# Power_5V.net
KiCad netlist of a schematic drawn in Altium Designer
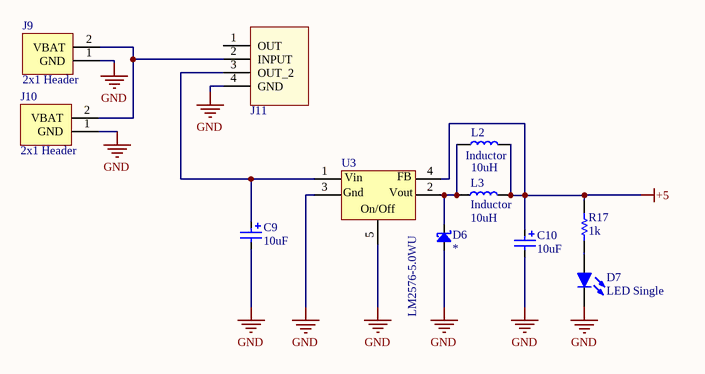
[diagram p0: Power 5V.SchDoc]

(export (version "E")
  (design (tool "Eeschema 10.0.6"))
  (components
    (comp (ref "C9")
      (value "10uF")
      (footprint "Capacitor Through Hole 5x11")
      (description "Capacitor")
      (libsource (lib "RK_Lib") (part "Capacitor Polarized"))
    )
    (comp (ref "C10")
      (value "10uF")
      (footprint "Through hole Capacitor 16V 470uF")
      (description "Capacitor")
      (libsource (lib "RK_Lib") (part "Capacitor Polarized"))
    )
    (comp (ref "D6")
      (value "*")
      (footprint "Schottky Rectifier diode")
      (description "Diode Schottky")
      (libsource (lib "RK_Lib") (part "Diode Schottky"))
    )
    (comp (ref "D7")
      (value "LED Single")
      (footprint "LED 0603")
      (description "LED")
      (libsource (lib "RK_Lib") (part "LED Single"))
    )
    (comp (ref "J9")
      (value "2x1 Header")
      (footprint "Header 1x2 2.54mm")
      (libsource (lib "RK_Lib") (part "2x1 Header (power)"))
    )
    (comp (ref "J10")
      (value "2x1 Header")
      (footprint "Header 1x2 2.54mm")
      (libsource (lib "RK_Lib") (part "2x1 Header (power)"))
    )
    (comp (ref "J11")
      (value "Power Switch")
      (footprint "POWER SWITCH")
      (libsource (lib "RK_Lib") (part "Power Switch"))
    )
    (comp (ref "L2")
      (value "Inductor")
      (footprint "Inductor 12.5x12.5x6mm")
      (fields (field (name "ALTIUM_VALUE") "10uH"))
      (libsource (lib "RK_Lib") (part "Inductor"))
    )
    (comp (ref "L3")
      (value "Inductor")
      (footprint "Inductor 12.5x12.5x6mm")
      (fields (field (name "ALTIUM_VALUE") "10uH"))
      (libsource (lib "RK_Lib") (part "Inductor"))
    )
    (comp (ref "R17")
      (value "1k")
      (footprint "R 0603")
      (description "Resistor")
      (libsource (lib "RK_Lib") (part "Res"))
    )
    (comp (ref "U3")
      (value "LM2576-5.0WU")
      (footprint "5V 3A REG")
      (description "IC REG BUCK 5V 3A TO263-5")
      (fields (field (name "MANUFACTURER") "Microchip Micrel"))
      (libsource (lib "RK_Lib") (part "LM2576-5.0WU"))
    )
  )
  (nets
    (net (code "1") (name "+5") (class "Default")
      (node (ref "C10") (pin "1") (pinfunction "1_1") (pintype "passive"))
      (node (ref "L2") (pin "2") (pinfunction "2_2") (pintype "passive"))
      (node (ref "L3") (pin "2") (pinfunction "2_2") (pintype "passive"))
      (node (ref "R17") (pin "1") (pinfunction "1_1") (pintype "passive"))
      (node (ref "U3") (pin "4") (pinfunction "4_4") (pintype "passive"))
    )
    (net (code "2") (name "GND") (class "Default")
      (node (ref "C10") (pin "2") (pinfunction "2_2") (pintype "passive"))
      (node (ref "C9") (pin "2") (pinfunction "2_2") (pintype "passive"))
      (node (ref "D6") (pin "2") (pinfunction "A_2") (pintype "passive"))
      (node (ref "D7") (pin "2") (pinfunction "K_2") (pintype "passive"))
      (node (ref "J10") (pin "1") (pinfunction "GND_1") (pintype "power_in"))
      (node (ref "J11") (pin "4") (pinfunction "GND_4") (pintype "passive"))
      (node (ref "J9") (pin "1") (pinfunction "GND_1") (pintype "power_in"))
      (node (ref "U3") (pin "3") (pinfunction "3_3") (pintype "passive"))
      (node (ref "U3") (pin "5") (pinfunction "5_5") (pintype "passive"))
    )
    (net (code "3") (name "Net-(D6-K)") (class "Default")
      (node (ref "D6") (pin "1") (pinfunction "K_1") (pintype "passive"))
      (node (ref "L2") (pin "1") (pinfunction "1_1") (pintype "passive"))
      (node (ref "L3") (pin "1") (pinfunction "1_1") (pintype "passive"))
      (node (ref "U3") (pin "2") (pinfunction "2_2") (pintype "passive"))
    )
    (net (code "4") (name "Net-(D7-A)") (class "Default")
      (node (ref "D7") (pin "1") (pinfunction "A_1") (pintype "passive"))
      (node (ref "R17") (pin "2") (pinfunction "2_2") (pintype "passive"))
    )
    (net (code "5") (name "Net-(J10-VBAT)") (class "Default")
      (node (ref "J10") (pin "2") (pinfunction "VBAT_2") (pintype "power_in"))
      (node (ref "J11") (pin "2") (pinfunction "INPUT_2") (pintype "passive"))
      (node (ref "J9") (pin "2") (pinfunction "VBAT_2") (pintype "power_in"))
    )
    (net (code "6") (name "Net-(J11-OUT_2)") (class "Default")
      (node (ref "C9") (pin "1") (pinfunction "1_1") (pintype "passive"))
      (node (ref "J11") (pin "3") (pinfunction "OUT_2_3") (pintype "passive"))
      (node (ref "U3") (pin "1") (pinfunction "1_1") (pintype "passive"))
    )
    (net (code "7") (name "unconnected-(J11-OUT-Pad1)") (class "Default")
      (node (ref "J11") (pin "1") (pinfunction "OUT_1") (pintype "passive"))
    )
  )
)
